# Sheet_clock_circuite.net
KiCad netlist of a schematic drawn in Altium Designer
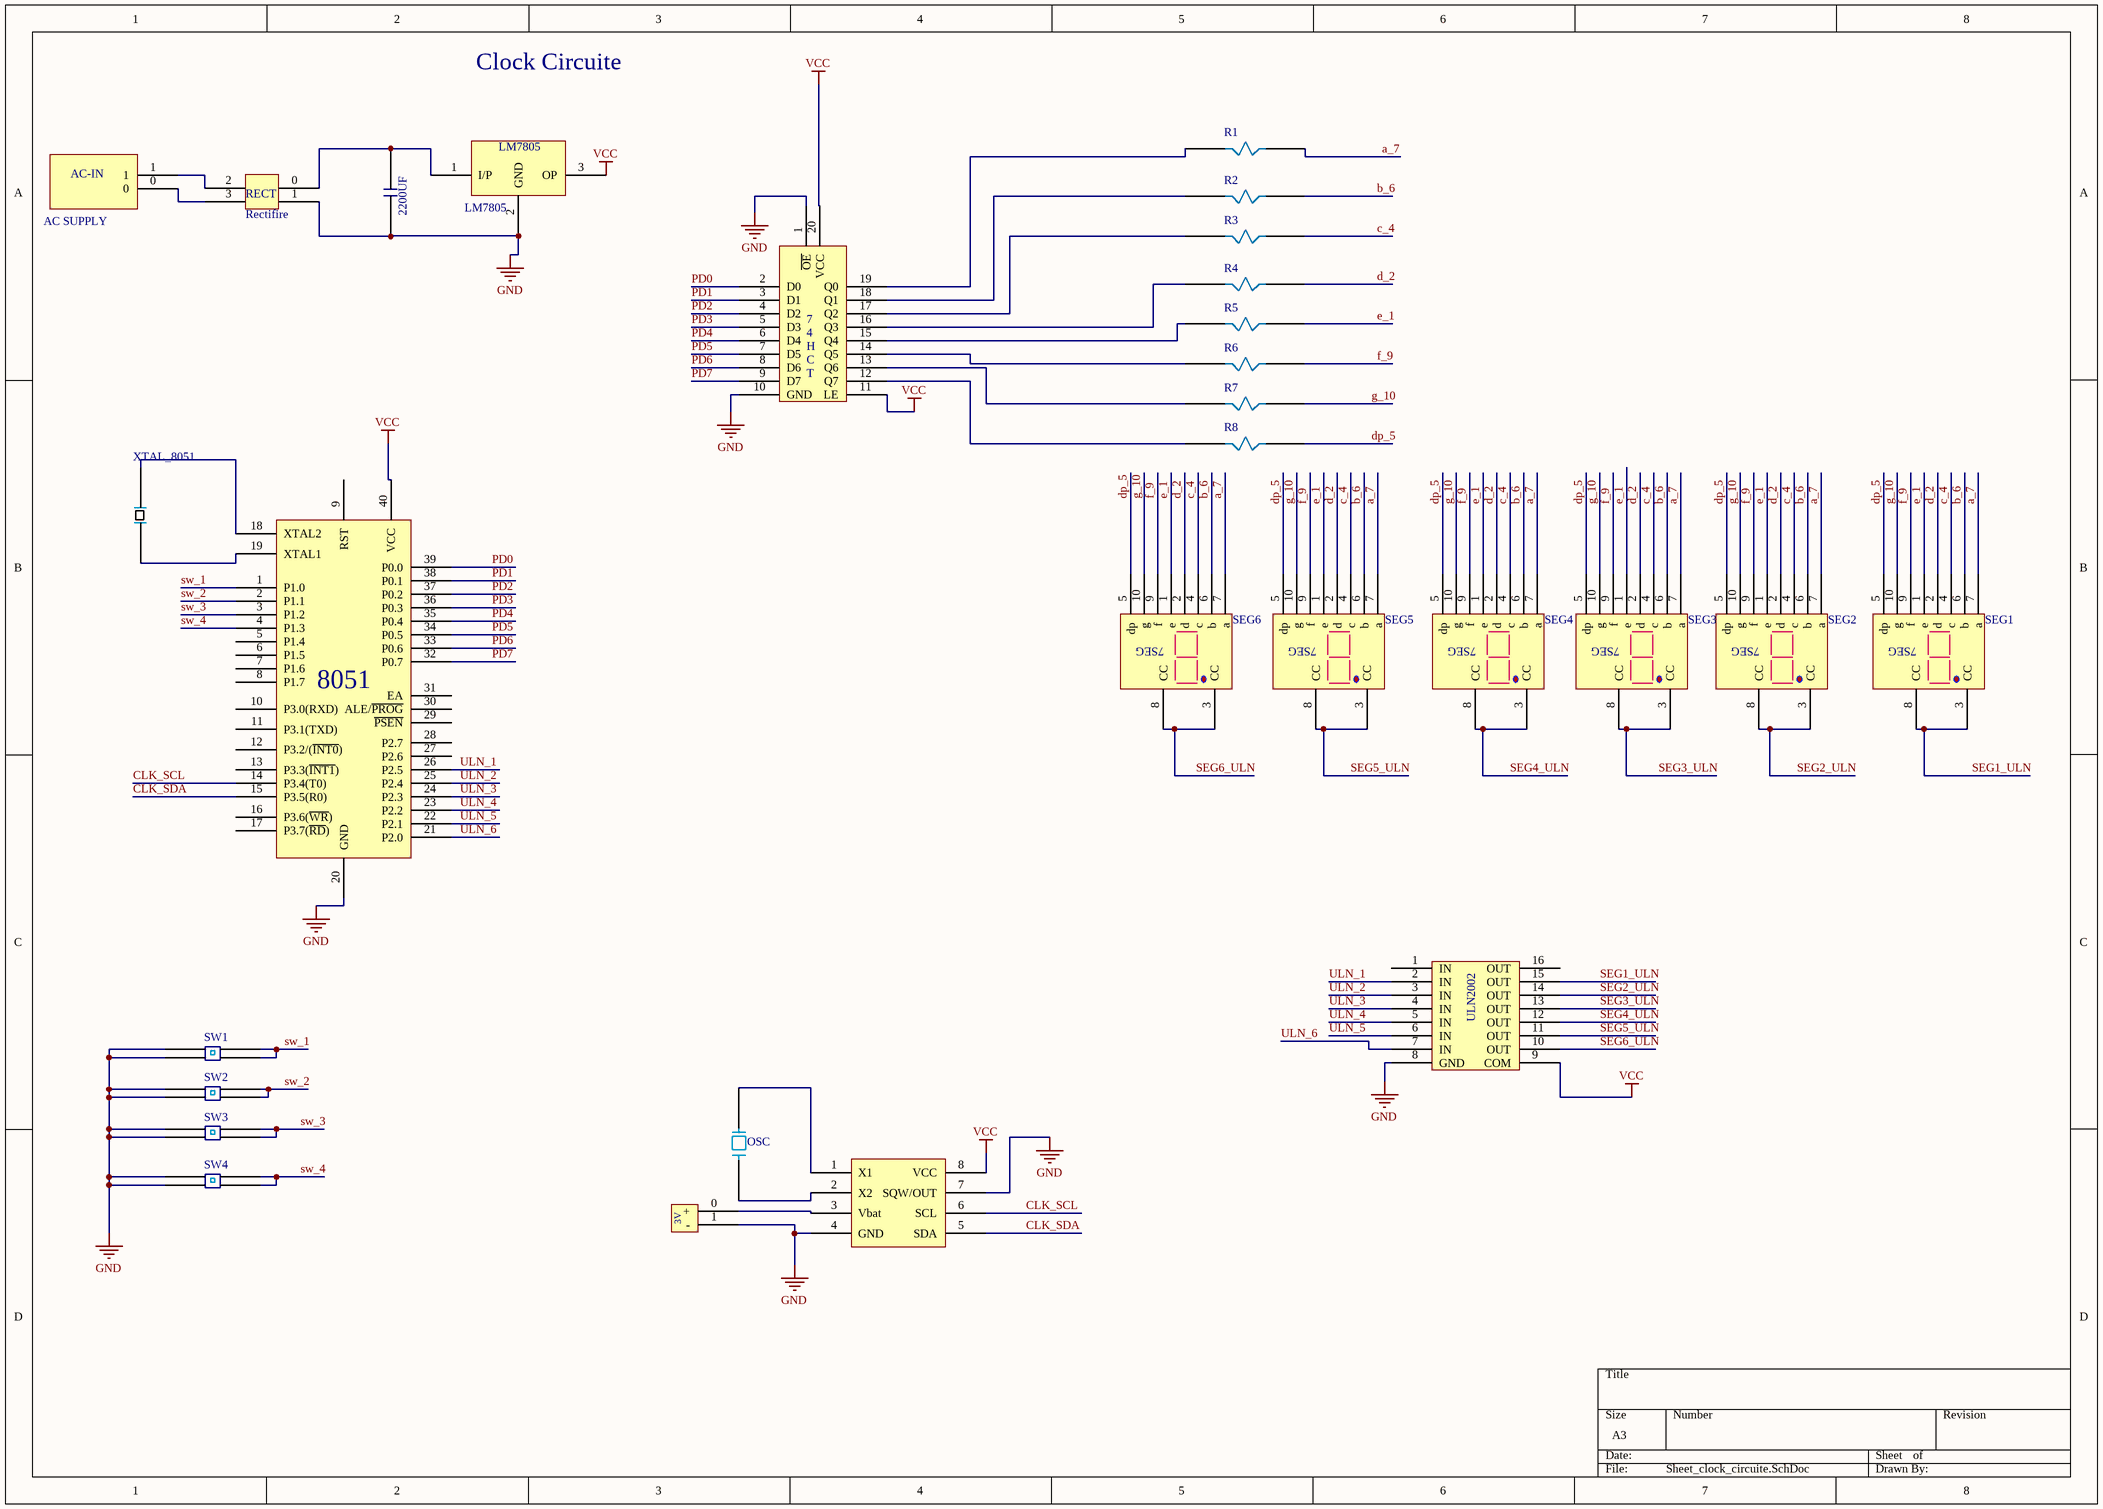
[diagram p0: Sheet_clock_circuite.SchDoc]

(export (version "E")
  (design (tool "Eeschema 10.0.6"))
  (components
    (comp (ref "3V") (value "Battery_3V") (footprint "3V BAT") (libsource (lib "MY LIB") (part "Battery_3V")))
    (comp (ref "74HCT") (value "74_HCT") (footprint "74HCT") (libsource (lib "MY LIB") (part "74_HCT")))
    (comp (ref "7805") (value "LM7805") (footprint "L7805") (libsource (lib "MY LIB") (part "LM7805")))
    (comp (ref "8051")
      (value "Microcontroller")
      (footprint "NUV_8051")
      (libsource (lib "MY LIB") (part "8051"))
    )
    (comp (ref "110592MHZ")
      (value "XTAL_8051")
      (footprint "osc_12")
      (libsource (lib "MY LIB") (part "XTAL_8051"))
    )
    (comp (ref "AC")
      (value "AC SUPPLY")
      (footprint "CONNECTOR")
      (libsource (lib "MY LIB") (part "AC SUPPLY"))
    )
    (comp (ref "CAP") (value "CF2200UF") (footprint "CAP2200UF") (libsource (lib "MY LIB") (part "CF2200UF")))
    (comp (ref "CLK")
      (value "DS1307_RTC")
      (footprint "DS1307")
      (libsource (lib "MY LIB") (part "DS1307_RTC"))
    )
    (comp (ref "OSC")
      (value "OSCILLATOR")
      (footprint "OSC_32K")
      (libsource (lib "MY LIB") (part "OSCILLATOR"))
    )
    (comp (ref "R1") (value "RES330") (footprint "RES") (libsource (lib "MY LIB") (part "RES330")))
    (comp (ref "R2") (value "RES330") (footprint "RES") (libsource (lib "MY LIB") (part "RES330")))
    (comp (ref "R3") (value "RES330") (footprint "RES") (libsource (lib "MY LIB") (part "RES330")))
    (comp (ref "R4") (value "RES330") (footprint "RES") (libsource (lib "MY LIB") (part "RES330")))
    (comp (ref "R5") (value "RES330") (footprint "RES") (libsource (lib "MY LIB") (part "RES330")))
    (comp (ref "R6") (value "RES330") (footprint "RES") (libsource (lib "MY LIB") (part "RES330")))
    (comp (ref "R7") (value "RES330") (footprint "RES") (libsource (lib "MY LIB") (part "RES330")))
    (comp (ref "R8") (value "RES330") (footprint "RES") (libsource (lib "MY LIB") (part "RES330")))
    (comp (ref "REC") (value "Rectifire") (footprint "RECT") (libsource (lib "MY LIB") (part "Rectifire")))
    (comp (ref "SEG1")
      (value "7SEGMENT")
      (footprint "LED_Display")
      (libsource (lib "MY LIB") (part "7-SEGMENTS"))
    )
    (comp (ref "SEG2")
      (value "7SEGMENT")
      (footprint "LED_Display")
      (libsource (lib "MY LIB") (part "7-SEGMENTS"))
    )
    (comp (ref "SEG3")
      (value "7SEGMENT")
      (footprint "LED_Display")
      (libsource (lib "MY LIB") (part "7-SEGMENTS"))
    )
    (comp (ref "SEG4")
      (value "7SEGMENT")
      (footprint "LED_Display")
      (libsource (lib "MY LIB") (part "7-SEGMENTS"))
    )
    (comp (ref "SEG5")
      (value "7SEGMENT")
      (footprint "LED_Display")
      (libsource (lib "MY LIB") (part "7-SEGMENTS"))
    )
    (comp (ref "SEG6")
      (value "7SEGMENT")
      (footprint "LED_Display")
      (libsource (lib "MY LIB") (part "7-SEGMENTS"))
    )
    (comp (ref "SW1") (value "SWITCH") (footprint "SWITCH") (libsource (lib "MY LIB") (part "SWITCH")))
    (comp (ref "SW2") (value "SWITCH") (footprint "SWITCH") (libsource (lib "MY LIB") (part "SWITCH")))
    (comp (ref "SW3") (value "SWITCH") (footprint "SWITCH") (libsource (lib "MY LIB") (part "SWITCH")))
    (comp (ref "SW4") (value "SWITCH") (footprint "SWITCH") (libsource (lib "MY LIB") (part "SWITCH")))
    (comp (ref "uln") (value "ULN2002") (footprint "ULN2002") (libsource (lib "MY LIB") (part "ULN2002")))
  )
  (nets
    (net (code "1") (name "/CLK_SCL") (class "Default")
      (node (ref "8051") (pin "14") (pinfunction "P3.4(T0)_14") (pintype "passive"))
      (node (ref "CLK") (pin "6") (pinfunction "SCL_6") (pintype "passive"))
    )
    (net (code "2") (name "/CLK_SDA") (class "Default")
      (node (ref "8051") (pin "15") (pinfunction "P3.5(R0)_15") (pintype "passive"))
      (node (ref "CLK") (pin "5") (pinfunction "SDA_5") (pintype "passive"))
    )
    (net (code "3") (name "/PD0") (class "Default")
      (node (ref "74HCT") (pin "2") (pinfunction "D0_2") (pintype "passive"))
      (node (ref "8051") (pin "39") (pinfunction "P0.0_39") (pintype "passive"))
    )
    (net (code "4") (name "/PD1") (class "Default")
      (node (ref "74HCT") (pin "3") (pinfunction "D1_3") (pintype "passive"))
      (node (ref "8051") (pin "38") (pinfunction "P0.1_38") (pintype "passive"))
    )
    (net (code "5") (name "/PD2") (class "Default")
      (node (ref "74HCT") (pin "4") (pinfunction "D2_4") (pintype "passive"))
      (node (ref "8051") (pin "37") (pinfunction "P0.2_37") (pintype "passive"))
    )
    (net (code "6") (name "/PD3") (class "Default")
      (node (ref "74HCT") (pin "5") (pinfunction "D3_5") (pintype "passive"))
      (node (ref "8051") (pin "36") (pinfunction "P0.3_36") (pintype "passive"))
    )
    (net (code "7") (name "/PD4") (class "Default")
      (node (ref "74HCT") (pin "6") (pinfunction "D4_6") (pintype "passive"))
      (node (ref "8051") (pin "35") (pinfunction "P0.4_35") (pintype "passive"))
    )
    (net (code "8") (name "/PD5") (class "Default")
      (node (ref "74HCT") (pin "7") (pinfunction "D5_7") (pintype "passive"))
      (node (ref "8051") (pin "34") (pinfunction "P0.5_34") (pintype "passive"))
    )
    (net (code "9") (name "/PD6") (class "Default")
      (node (ref "74HCT") (pin "8") (pinfunction "D6_8") (pintype "passive"))
      (node (ref "8051") (pin "33") (pinfunction "P0.6_33") (pintype "passive"))
    )
    (net (code "10") (name "/PD7") (class "Default")
      (node (ref "74HCT") (pin "9") (pinfunction "D7_9") (pintype "passive"))
      (node (ref "8051") (pin "32") (pinfunction "P0.7_32") (pintype "passive"))
    )
    (net (code "11") (name "/SEG1_ULN") (class "Default")
      (node (ref "SEG1") (pin "3") (pinfunction "CC_3") (pintype "passive"))
      (node (ref "SEG1") (pin "8") (pinfunction "CC_8") (pintype "passive"))
      (node (ref "uln") (pin "15") (pinfunction "OUT_15") (pintype "passive"))
    )
    (net (code "12") (name "/SEG2_ULN") (class "Default")
      (node (ref "SEG2") (pin "3") (pinfunction "CC_3") (pintype "passive"))
      (node (ref "SEG2") (pin "8") (pinfunction "CC_8") (pintype "passive"))
      (node (ref "uln") (pin "14") (pinfunction "OUT_14") (pintype "passive"))
    )
    (net (code "13") (name "/SEG3_ULN") (class "Default")
      (node (ref "SEG3") (pin "3") (pinfunction "CC_3") (pintype "passive"))
      (node (ref "SEG3") (pin "8") (pinfunction "CC_8") (pintype "passive"))
      (node (ref "uln") (pin "13") (pinfunction "OUT_13") (pintype "passive"))
    )
    (net (code "14") (name "/SEG4_ULN") (class "Default")
      (node (ref "SEG4") (pin "3") (pinfunction "CC_3") (pintype "passive"))
      (node (ref "SEG4") (pin "8") (pinfunction "CC_8") (pintype "passive"))
      (node (ref "uln") (pin "12") (pinfunction "OUT_12") (pintype "passive"))
    )
    (net (code "15") (name "/SEG5_ULN") (class "Default")
      (node (ref "SEG5") (pin "3") (pinfunction "CC_3") (pintype "passive"))
      (node (ref "SEG5") (pin "8") (pinfunction "CC_8") (pintype "passive"))
      (node (ref "uln") (pin "11") (pinfunction "OUT_11") (pintype "passive"))
    )
    (net (code "16") (name "/SEG6_ULN") (class "Default")
      (node (ref "SEG6") (pin "3") (pinfunction "CC_3") (pintype "passive"))
      (node (ref "SEG6") (pin "8") (pinfunction "CC_8") (pintype "passive"))
      (node (ref "uln") (pin "10") (pinfunction "OUT_10") (pintype "passive"))
    )
    (net (code "17") (name "/ULN_1") (class "Default")
      (node (ref "8051") (pin "26") (pinfunction "P2.5_26") (pintype "passive"))
      (node (ref "uln") (pin "2") (pinfunction "IN_2") (pintype "passive"))
    )
    (net (code "18") (name "/ULN_2") (class "Default")
      (node (ref "8051") (pin "25") (pinfunction "P2.4_25") (pintype "passive"))
      (node (ref "uln") (pin "3") (pinfunction "IN_3") (pintype "passive"))
    )
    (net (code "19") (name "/ULN_3") (class "Default")
      (node (ref "8051") (pin "24") (pinfunction "P2.3_24") (pintype "passive"))
      (node (ref "uln") (pin "4") (pinfunction "IN_4") (pintype "passive"))
    )
    (net (code "20") (name "/ULN_4") (class "Default")
      (node (ref "8051") (pin "23") (pinfunction "P2.2_23") (pintype "passive"))
      (node (ref "uln") (pin "5") (pinfunction "IN_5") (pintype "passive"))
    )
    (net (code "21") (name "/ULN_5") (class "Default")
      (node (ref "8051") (pin "22") (pinfunction "P2.1_22") (pintype "passive"))
      (node (ref "uln") (pin "6") (pinfunction "IN_6") (pintype "passive"))
    )
    (net (code "22") (name "/ULN_6") (class "Default")
      (node (ref "8051") (pin "21") (pinfunction "P2.0_21") (pintype "passive"))
      (node (ref "uln") (pin "7") (pinfunction "IN_7") (pintype "passive"))
    )
    (net (code "23") (name "/a_7") (class "Default")
      (node (ref "R1") (pin "1") (pinfunction "1_1") (pintype "passive"))
      (node (ref "SEG1") (pin "7") (pinfunction "a_7") (pintype "passive"))
      (node (ref "SEG2") (pin "7") (pinfunction "a_7") (pintype "passive"))
      (node (ref "SEG3") (pin "7") (pinfunction "a_7") (pintype "passive"))
      (node (ref "SEG4") (pin "7") (pinfunction "a_7") (pintype "passive"))
      (node (ref "SEG5") (pin "7") (pinfunction "a_7") (pintype "passive"))
      (node (ref "SEG6") (pin "7") (pinfunction "a_7") (pintype "passive"))
    )
    (net (code "24") (name "/b_6") (class "Default")
      (node (ref "R2") (pin "1") (pinfunction "1_1") (pintype "passive"))
      (node (ref "SEG1") (pin "6") (pinfunction "b_6") (pintype "passive"))
      (node (ref "SEG2") (pin "6") (pinfunction "b_6") (pintype "passive"))
      (node (ref "SEG3") (pin "6") (pinfunction "b_6") (pintype "passive"))
      (node (ref "SEG4") (pin "6") (pinfunction "b_6") (pintype "passive"))
      (node (ref "SEG5") (pin "6") (pinfunction "b_6") (pintype "passive"))
      (node (ref "SEG6") (pin "6") (pinfunction "b_6") (pintype "passive"))
    )
    (net (code "25") (name "/c_4") (class "Default")
      (node (ref "R3") (pin "1") (pinfunction "1_1") (pintype "passive"))
      (node (ref "SEG1") (pin "4") (pinfunction "c_4") (pintype "passive"))
      (node (ref "SEG2") (pin "4") (pinfunction "c_4") (pintype "passive"))
      (node (ref "SEG3") (pin "4") (pinfunction "c_4") (pintype "passive"))
      (node (ref "SEG4") (pin "4") (pinfunction "c_4") (pintype "passive"))
      (node (ref "SEG5") (pin "4") (pinfunction "c_4") (pintype "passive"))
      (node (ref "SEG6") (pin "4") (pinfunction "c_4") (pintype "passive"))
    )
    (net (code "26") (name "/d_2") (class "Default")
      (node (ref "R4") (pin "1") (pinfunction "1_1") (pintype "passive"))
      (node (ref "SEG1") (pin "2") (pinfunction "d_2") (pintype "passive"))
      (node (ref "SEG2") (pin "2") (pinfunction "d_2") (pintype "passive"))
      (node (ref "SEG3") (pin "2") (pinfunction "d_2") (pintype "passive"))
      (node (ref "SEG4") (pin "2") (pinfunction "d_2") (pintype "passive"))
      (node (ref "SEG5") (pin "2") (pinfunction "d_2") (pintype "passive"))
      (node (ref "SEG6") (pin "2") (pinfunction "d_2") (pintype "passive"))
    )
    (net (code "27") (name "/dp_5") (class "Default")
      (node (ref "R8") (pin "1") (pinfunction "1_1") (pintype "passive"))
      (node (ref "SEG1") (pin "5") (pinfunction "dp_5") (pintype "passive"))
      (node (ref "SEG2") (pin "5") (pinfunction "dp_5") (pintype "passive"))
      (node (ref "SEG3") (pin "5") (pinfunction "dp_5") (pintype "passive"))
      (node (ref "SEG4") (pin "5") (pinfunction "dp_5") (pintype "passive"))
      (node (ref "SEG5") (pin "5") (pinfunction "dp_5") (pintype "passive"))
      (node (ref "SEG6") (pin "5") (pinfunction "dp_5") (pintype "passive"))
    )
    (net (code "28") (name "/e_1") (class "Default")
      (node (ref "R5") (pin "1") (pinfunction "1_1") (pintype "passive"))
      (node (ref "SEG1") (pin "1") (pinfunction "e_1") (pintype "passive"))
      (node (ref "SEG2") (pin "1") (pinfunction "e_1") (pintype "passive"))
      (node (ref "SEG3") (pin "1") (pinfunction "e_1") (pintype "passive"))
      (node (ref "SEG4") (pin "1") (pinfunction "e_1") (pintype "passive"))
      (node (ref "SEG5") (pin "1") (pinfunction "e_1") (pintype "passive"))
      (node (ref "SEG6") (pin "1") (pinfunction "e_1") (pintype "passive"))
    )
    (net (code "29") (name "/f_9") (class "Default")
      (node (ref "R6") (pin "1") (pinfunction "1_1") (pintype "passive"))
      (node (ref "SEG1") (pin "9") (pinfunction "f_9") (pintype "passive"))
      (node (ref "SEG2") (pin "9") (pinfunction "f_9") (pintype "passive"))
      (node (ref "SEG3") (pin "9") (pinfunction "f_9") (pintype "passive"))
      (node (ref "SEG4") (pin "9") (pinfunction "f_9") (pintype "passive"))
      (node (ref "SEG5") (pin "9") (pinfunction "f_9") (pintype "passive"))
      (node (ref "SEG6") (pin "9") (pinfunction "f_9") (pintype "passive"))
    )
    (net (code "30") (name "/g_10") (class "Default")
      (node (ref "R7") (pin "1") (pinfunction "1_1") (pintype "passive"))
      (node (ref "SEG1") (pin "10") (pinfunction "g_10") (pintype "passive"))
      (node (ref "SEG2") (pin "10") (pinfunction "g_10") (pintype "passive"))
      (node (ref "SEG3") (pin "10") (pinfunction "g_10") (pintype "passive"))
      (node (ref "SEG4") (pin "10") (pinfunction "g_10") (pintype "passive"))
      (node (ref "SEG5") (pin "10") (pinfunction "g_10") (pintype "passive"))
      (node (ref "SEG6") (pin "10") (pinfunction "g_10") (pintype "passive"))
    )
    (net (code "31") (name "/sw_1") (class "Default")
      (node (ref "8051") (pin "1") (pinfunction "P1.0_1") (pintype "passive"))
      (node (ref "SW1") (pin "2") (pinfunction "2_2") (pintype "passive"))
      (node (ref "SW1") (pin "3") (pinfunction "3_3") (pintype "passive"))
    )
    (net (code "32") (name "/sw_2") (class "Default")
      (node (ref "8051") (pin "2") (pinfunction "P1.1_2") (pintype "passive"))
      (node (ref "SW2") (pin "2") (pinfunction "2_2") (pintype "passive"))
      (node (ref "SW2") (pin "3") (pinfunction "3_3") (pintype "passive"))
    )
    (net (code "33") (name "/sw_3") (class "Default")
      (node (ref "8051") (pin "3") (pinfunction "P1.2_3") (pintype "passive"))
      (node (ref "SW3") (pin "2") (pinfunction "2_2") (pintype "passive"))
      (node (ref "SW3") (pin "3") (pinfunction "3_3") (pintype "passive"))
    )
    (net (code "34") (name "/sw_4") (class "Default")
      (node (ref "8051") (pin "4") (pinfunction "P1.3_4") (pintype "passive"))
      (node (ref "SW4") (pin "2") (pinfunction "2_2") (pintype "passive"))
      (node (ref "SW4") (pin "3") (pinfunction "3_3") (pintype "passive"))
    )
    (net (code "35") (name "GND") (class "Default")
      (node (ref "3V") (pin "1") (pinfunction "-_1") (pintype "passive"))
      (node (ref "74HCT") (pin "1") (pinfunction "~{OE}_1") (pintype "passive"))
      (node (ref "74HCT") (pin "10") (pinfunction "GND_10") (pintype "passive"))
      (node (ref "7805") (pin "2") (pinfunction "GND_2") (pintype "passive"))
      (node (ref "8051") (pin "20") (pinfunction "GND_20") (pintype "passive"))
      (node (ref "CAP") (pin "1") (pinfunction "1_1") (pintype "passive"))
      (node (ref "CLK") (pin "4") (pinfunction "GND_4") (pintype "passive"))
      (node (ref "CLK") (pin "7") (pinfunction "SQW/OUT_7") (pintype "passive"))
      (node (ref "REC") (pin "1") (pinfunction "1_1") (pintype "passive"))
      (node (ref "SW1") (pin "0") (pinfunction "0_0") (pintype "passive"))
      (node (ref "SW1") (pin "1") (pinfunction "1_1") (pintype "passive"))
      (node (ref "SW2") (pin "0") (pinfunction "0_0") (pintype "passive"))
      (node (ref "SW2") (pin "1") (pinfunction "1_1") (pintype "passive"))
      (node (ref "SW3") (pin "0") (pinfunction "0_0") (pintype "passive"))
      (node (ref "SW3") (pin "1") (pinfunction "1_1") (pintype "passive"))
      (node (ref "SW4") (pin "0") (pinfunction "0_0") (pintype "passive"))
      (node (ref "SW4") (pin "1") (pinfunction "1_1") (pintype "passive"))
      (node (ref "uln") (pin "8") (pinfunction "GND_8") (pintype "passive"))
    )
    (net (code "36") (name "Net-(3V-+)") (class "Default")
      (node (ref "3V") (pin "0") (pinfunction "+_0") (pintype "passive"))
      (node (ref "CLK") (pin "3") (pinfunction "Vbat_3") (pintype "passive"))
    )
    (net (code "37") (name "Net-(74HCT-Q0)") (class "Default")
      (node (ref "74HCT") (pin "19") (pinfunction "Q0_19") (pintype "passive"))
      (node (ref "R1") (pin "0") (pinfunction "0_0") (pintype "passive"))
    )
    (net (code "38") (name "Net-(74HCT-Q1)") (class "Default")
      (node (ref "74HCT") (pin "18") (pinfunction "Q1_18") (pintype "passive"))
      (node (ref "R2") (pin "0") (pinfunction "0_0") (pintype "passive"))
    )
    (net (code "39") (name "Net-(74HCT-Q2)") (class "Default")
      (node (ref "74HCT") (pin "17") (pinfunction "Q2_17") (pintype "passive"))
      (node (ref "R3") (pin "0") (pinfunction "0_0") (pintype "passive"))
    )
    (net (code "40") (name "Net-(74HCT-Q3)") (class "Default")
      (node (ref "74HCT") (pin "16") (pinfunction "Q3_16") (pintype "passive"))
      (node (ref "R4") (pin "0") (pinfunction "0_0") (pintype "passive"))
    )
    (net (code "41") (name "Net-(74HCT-Q4)") (class "Default")
      (node (ref "74HCT") (pin "15") (pinfunction "Q4_15") (pintype "passive"))
      (node (ref "R5") (pin "0") (pinfunction "0_0") (pintype "passive"))
    )
    (net (code "42") (name "Net-(74HCT-Q5)") (class "Default")
      (node (ref "74HCT") (pin "14") (pinfunction "Q5_14") (pintype "passive"))
      (node (ref "R6") (pin "0") (pinfunction "0_0") (pintype "passive"))
    )
    (net (code "43") (name "Net-(74HCT-Q6)") (class "Default")
      (node (ref "74HCT") (pin "13") (pinfunction "Q6_13") (pintype "passive"))
      (node (ref "R7") (pin "0") (pinfunction "0_0") (pintype "passive"))
    )
    (net (code "44") (name "Net-(74HCT-Q7)") (class "Default")
      (node (ref "74HCT") (pin "12") (pinfunction "Q7_12") (pintype "passive"))
      (node (ref "R8") (pin "0") (pinfunction "0_0") (pintype "passive"))
    )
    (net (code "45") (name "Net-(7805-I{slash}P)") (class "Default")
      (node (ref "7805") (pin "1") (pinfunction "I/P_1") (pintype "passive"))
      (node (ref "CAP") (pin "0") (pinfunction "0_0") (pintype "passive"))
      (node (ref "REC") (pin "0") (pinfunction "0_0") (pintype "passive"))
    )
    (net (code "46") (name "Net-(8051-XTAL1)") (class "Default")
      (node (ref "110592MHZ") (pin "0") (pinfunction "0_0") (pintype "passive"))
      (node (ref "8051") (pin "19") (pinfunction "XTAL1_19") (pintype "passive"))
    )
    (net (code "47") (name "Net-(8051-XTAL2)") (class "Default")
      (node (ref "110592MHZ") (pin "1") (pinfunction "1_1") (pintype "passive"))
      (node (ref "8051") (pin "18") (pinfunction "XTAL2_18") (pintype "passive"))
    )
    (net (code "48") (name "Net-(AC-Pad0)") (class "Default")
      (node (ref "AC") (pin "0") (pinfunction "0_0") (pintype "passive"))
      (node (ref "REC") (pin "3") (pinfunction "3_3") (pintype "passive"))
    )
    (net (code "49") (name "Net-(AC-Pad1)") (class "Default")
      (node (ref "AC") (pin "1") (pinfunction "1_1") (pintype "passive"))
      (node (ref "REC") (pin "2") (pinfunction "2_2") (pintype "passive"))
    )
    (net (code "50") (name "Net-(CLK-X1)") (class "Default")
      (node (ref "CLK") (pin "1") (pinfunction "X1_1") (pintype "passive"))
      (node (ref "OSC") (pin "1") (pinfunction "1_1") (pintype "passive"))
    )
    (net (code "51") (name "Net-(CLK-X2)") (class "Default")
      (node (ref "CLK") (pin "2") (pinfunction "X2_2") (pintype "passive"))
      (node (ref "OSC") (pin "0") (pinfunction "0_0") (pintype "passive"))
    )
    (net (code "52") (name "VCC") (class "Default")
      (node (ref "74HCT") (pin "11") (pinfunction "LE_11") (pintype "passive"))
      (node (ref "74HCT") (pin "20") (pinfunction "VCC_20") (pintype "passive"))
      (node (ref "7805") (pin "3") (pinfunction "OP_3") (pintype "passive"))
      (node (ref "8051") (pin "40") (pinfunction "VCC_40") (pintype "passive"))
      (node (ref "CLK") (pin "8") (pinfunction "VCC_8") (pintype "passive"))
      (node (ref "uln") (pin "9") (pinfunction "COM_9") (pintype "passive"))
    )
    (net (code "53") (name "unconnected-(8051-ALE{slash}~{PROG}-Pad30)") (class "Default")
      (node (ref "8051") (pin "30") (pinfunction "ALE/~{PROG}_30") (pintype "passive"))
    )
    (net (code "54") (name "unconnected-(8051-EA-Pad31)") (class "Default")
      (node (ref "8051") (pin "31") (pinfunction "EA_31") (pintype "passive"))
    )
    (net (code "55") (name "unconnected-(8051-P1.4-Pad5)") (class "Default")
      (node (ref "8051") (pin "5") (pinfunction "P1.4_5") (pintype "passive"))
    )
    (net (code "56") (name "unconnected-(8051-P1.5-Pad6)") (class "Default")
      (node (ref "8051") (pin "6") (pinfunction "P1.5_6") (pintype "passive"))
    )
    (net (code "57") (name "unconnected-(8051-P1.6-Pad7)") (class "Default")
      (node (ref "8051") (pin "7") (pinfunction "P1.6_7") (pintype "passive"))
    )
    (net (code "58") (name "unconnected-(8051-P1.7-Pad8)") (class "Default")
      (node (ref "8051") (pin "8") (pinfunction "P1.7_8") (pintype "passive"))
    )
    (net (code "59") (name "unconnected-(8051-P2.6-Pad27)") (class "Default")
      (node (ref "8051") (pin "27") (pinfunction "P2.6_27") (pintype "passive"))
    )
    (net (code "60") (name "unconnected-(8051-P2.7-Pad28)") (class "Default")
      (node (ref "8051") (pin "28") (pinfunction "P2.7_28") (pintype "passive"))
    )
    (net (code "61") (name "unconnected-(8051-P3.0(RXD)-Pad10)") (class "Default")
      (node (ref "8051") (pin "10") (pinfunction "P3.0(RXD)_10") (pintype "passive"))
    )
    (net (code "62") (name "unconnected-(8051-P3.1(TXD)-Pad11)") (class "Default")
      (node (ref "8051") (pin "11") (pinfunction "P3.1(TXD)_11") (pintype "passive"))
    )
    (net (code "63") (name "unconnected-(8051-P3.2{slash}(~{INT0})-Pad12)") (class "Default")
      (node (ref "8051") (pin "12") (pinfunction "P3.2/(~{INT0})_12") (pintype "passive"))
    )
    (net (code "64") (name "unconnected-(8051-P3.3(~{INT1})-Pad13)") (class "Default")
      (node (ref "8051") (pin "13") (pinfunction "P3.3(~{INT1})_13") (pintype "passive"))
    )
    (net (code "65") (name "unconnected-(8051-P3.6(~{WR})-Pad16)") (class "Default")
      (node (ref "8051") (pin "16") (pinfunction "P3.6(~{WR})_16") (pintype "passive"))
    )
    (net (code "66") (name "unconnected-(8051-P3.7(~{RD})-Pad17)") (class "Default")
      (node (ref "8051") (pin "17") (pinfunction "P3.7(~{RD})_17") (pintype "passive"))
    )
    (net (code "67") (name "unconnected-(8051-RST-Pad9)") (class "Default")
      (node (ref "8051") (pin "9") (pinfunction "RST_9") (pintype "passive"))
    )
    (net (code "68") (name "unconnected-(8051-~{PSEN}-Pad29)") (class "Default")
      (node (ref "8051") (pin "29") (pinfunction "~{PSEN}_29") (pintype "passive"))
    )
    (net (code "69") (name "unconnected-(uln-IN-Pad1)") (class "Default")
      (node (ref "uln") (pin "1") (pinfunction "IN_1") (pintype "passive"))
    )
    (net (code "70") (name "unconnected-(uln-OUT-Pad16)") (class "Default")
      (node (ref "uln") (pin "16") (pinfunction "OUT_16") (pintype "passive"))
    )
  )
)
